# FU-AM-FU6861-B-025-HW-V1_0-20210601.net
KiCad netlist of a schematic drawn in Altium Designer
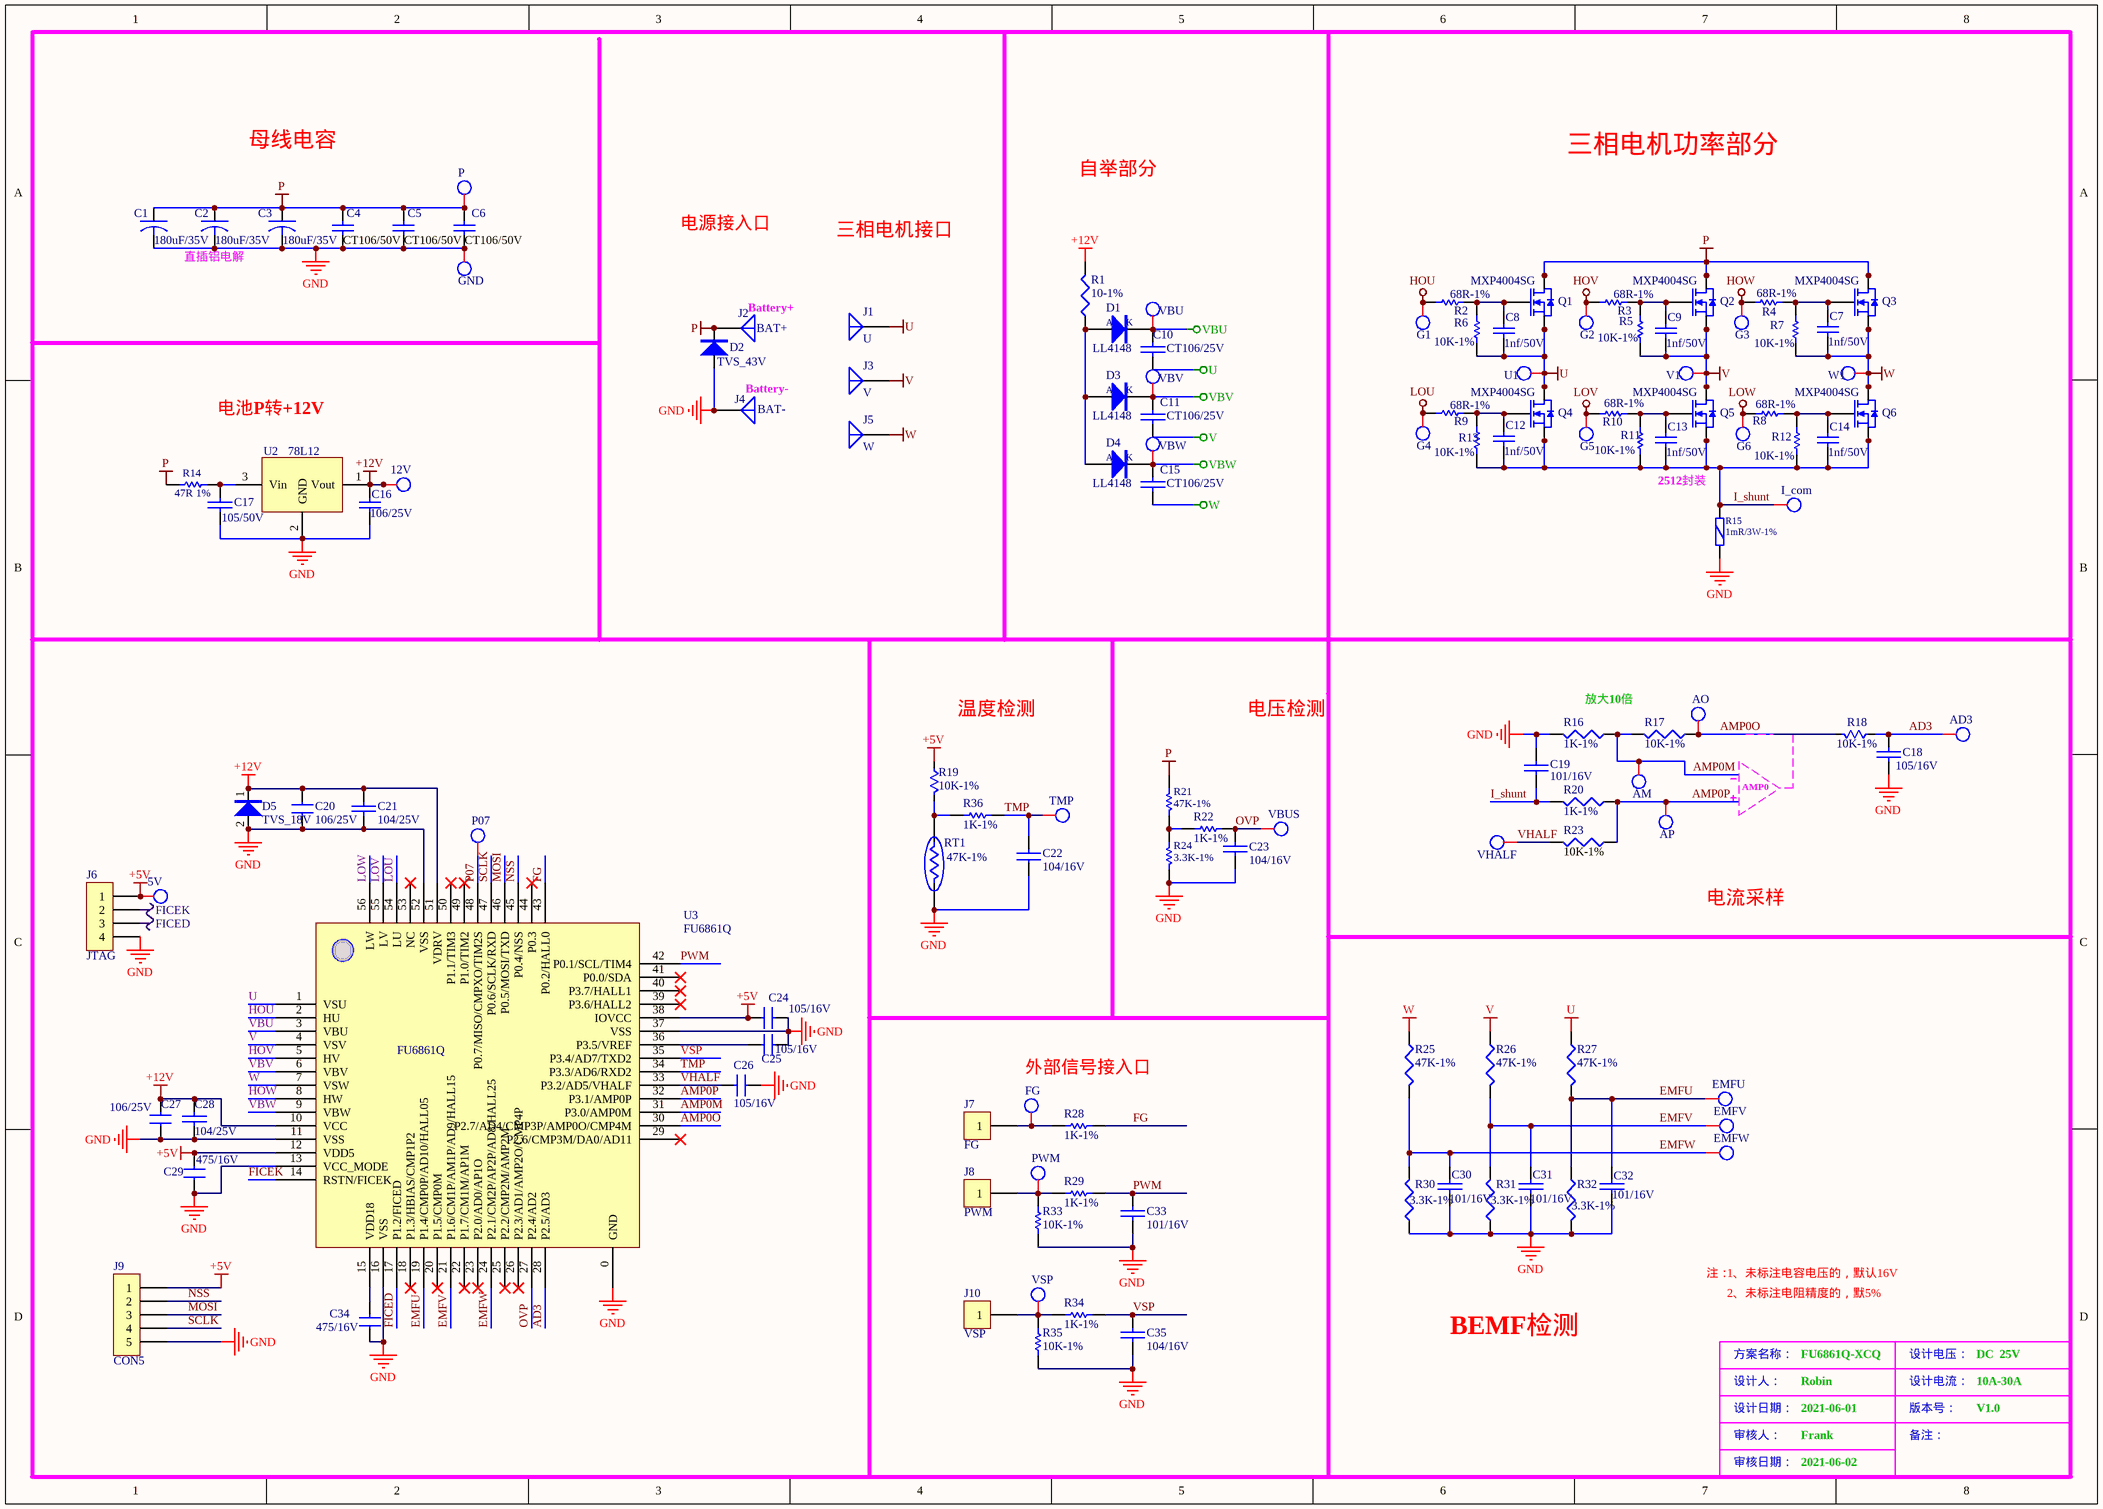
[diagram p0: FU-AM-FU6861-B-025-HW-V1.0-20210601.SCHDOC]

(export (version "E")
  (design (tool "Eeschema 10.0.6"))
  (components
    (comp (ref "5V") (value "~") (footprint "TP1.1") (libsource (lib "*") (part "Component_1")))
    (comp (ref "12V") (value "~") (footprint "TP1.1") (libsource (lib "*") (part "Component_1")))
    (comp (ref "AD3") (value "~") (footprint "TP1.1") (libsource (lib "*") (part "Component_1")))
    (comp (ref "AM") (value "~") (footprint "TP1.1") (libsource (lib "*") (part "Component_1")))
    (comp (ref "AO") (value "~") (footprint "TP1.1") (libsource (lib "*") (part "Component_1")))
    (comp (ref "AP") (value "~") (footprint "TP1.1") (libsource (lib "*") (part "Component_1")))
    (comp (ref "C1")
      (value "180uF/35V")
      (footprint "CAP2_5")
      (description "Capacitor")
      (libsource (lib "*") (part "CAPACITOR"))
    )
    (comp (ref "C2")
      (value "180uF/35V")
      (footprint "CAP2_5")
      (description "Capacitor")
      (libsource (lib "*") (part "CAPACITOR"))
    )
    (comp (ref "C3")
      (value "180uF/35V")
      (footprint "CAP2_5")
      (description "Capacitor")
      (libsource (lib "*") (part "CAPACITOR"))
    )
    (comp (ref "C4")
      (value "CT106/50V")
      (footprint "c1206")
      (description "YG-C1206K106-50V（10UF）-10%")
      (fields (field (name "PUBLISHER") "Altium Limited"))
      (libsource (lib "*") (part "Cap"))
    )
    (comp (ref "C5")
      (value "CT106/50V")
      (footprint "c1206")
      (description "YG-C1206K106-50V（10UF）-10%")
      (fields (field (name "PUBLISHER") "Altium Limited"))
      (libsource (lib "*") (part "Cap"))
    )
    (comp (ref "C6")
      (value "CT106/50V")
      (footprint "c1206")
      (description "YG-C1206K106-50V（10UF）-10%")
      (fields (field (name "PUBLISHER") "Altium Limited"))
      (libsource (lib "*") (part "Cap"))
    )
    (comp (ref "C7")
      (value "1nf/50V")
      (footprint "c0603")
      (description "YG-C1206K106-50V（10UF）-10%")
      (fields (field (name "PUBLISHER") "Altium Limited"))
      (libsource (lib "*") (part "Cap"))
    )
    (comp (ref "C8")
      (value "1nf/50V")
      (footprint "C0603")
      (description "YG-C1206K106-50V（10UF）-10%")
      (fields (field (name "PUBLISHER") "Altium Limited"))
      (libsource (lib "*") (part "Cap"))
    )
    (comp (ref "C9")
      (value "1nf/50V")
      (footprint "C0603")
      (description "YG-C1206K106-50V（10UF）-10%")
      (fields (field (name "PUBLISHER") "Altium Limited"))
      (libsource (lib "*") (part "Cap"))
    )
    (comp (ref "C10")
      (value "CT106/25V")
      (footprint "c0805")
      (description "Capacitor")
      (libsource (lib "*") (part "CAP-CC(SMD)"))
    )
    (comp (ref "C11")
      (value "CT106/25V")
      (footprint "c0805")
      (description "Capacitor")
      (libsource (lib "*") (part "CAP-CC(SMD)"))
    )
    (comp (ref "C12")
      (value "1nf/50V")
      (footprint "c0603")
      (description "YG-C1206K106-50V（10UF）-10%")
      (fields (field (name "PUBLISHER") "Altium Limited"))
      (libsource (lib "*") (part "Cap"))
    )
    (comp (ref "C13")
      (value "1nf/50V")
      (footprint "C0603")
      (description "YG-C1206K106-50V（10UF）-10%")
      (fields (field (name "PUBLISHER") "Altium Limited"))
      (libsource (lib "*") (part "Cap"))
    )
    (comp (ref "C14")
      (value "1nf/50V")
      (footprint "C0603")
      (description "YG-C1206K106-50V（10UF）-10%")
      (fields (field (name "PUBLISHER") "Altium Limited"))
      (libsource (lib "*") (part "Cap"))
    )
    (comp (ref "C15")
      (value "CT106/25V")
      (footprint "c0805")
      (description "Capacitor")
      (libsource (lib "*") (part "CAP-CC(SMD)"))
    )
    (comp (ref "C16")
      (value "106/25V")
      (footprint "C0805")
      (description "Capacitor (Semiconductor SIM Model)")
      (fields (field (name "PUBLISHER") "Altium Limited"))
      (libsource (lib "Miscellaneous Devices") (part "Cap Semi"))
    )
    (comp (ref "C17")
      (value "105/50V")
      (footprint "c1206")
      (description "Capacitor")
      (libsource (lib "") (part "CAP_2"))
    )
    (comp (ref "C18") (value "105/16V") (footprint "c0603") (libsource (lib "*") (part "CAP")))
    (comp (ref "C19")
      (value "101/16V")
      (footprint "c0603")
      (description "Capacitor")
      (libsource (lib "") (part "CAP_3"))
    )
    (comp (ref "C20")
      (value "106/25V")
      (footprint "c0805")
      (description "Capacitor")
      (libsource (lib "") (part "CAP_1"))
    )
    (comp (ref "C21")
      (value "104/25V")
      (footprint "c0603")
      (description "Capacitor")
      (libsource (lib "*") (part "CAP-CC"))
    )
    (comp (ref "C22") (value "104/16V") (footprint "c0603") (libsource (lib "*") (part "CAP NP")))
    (comp (ref "C23")
      (value "104/16V")
      (footprint "c0603")
      (description "Capacitor")
      (libsource (lib "") (part "CAP_2"))
    )
    (comp (ref "C24")
      (value "105/16V")
      (footprint "c0603")
      (description "Capacitor")
      (libsource (lib "") (part "CAP_1"))
    )
    (comp (ref "C25")
      (value "105/16V")
      (footprint "c0603")
      (description "Capacitor")
      (libsource (lib "") (part "CAP_1"))
    )
    (comp (ref "C26")
      (value "105/16V")
      (footprint "c0603")
      (description "Capacitor")
      (libsource (lib "") (part "CAP_1"))
    )
    (comp (ref "C27")
      (value "106/25V")
      (footprint "c0805")
      (description "Capacitor")
      (libsource (lib "") (part "CAP_1"))
    )
    (comp (ref "C28")
      (value "104/25V")
      (footprint "c0603")
      (description "Capacitor")
      (libsource (lib "*") (part "CAP-CC"))
    )
    (comp (ref "C29")
      (value "475/16V")
      (footprint "c0603")
      (description "Capacitor")
      (libsource (lib "") (part "CAP_1"))
    )
    (comp (ref "C30")
      (value "101/16V")
      (footprint "c0603")
      (description "Capacitor")
      (libsource (lib "") (part "CAP_3"))
    )
    (comp (ref "C31")
      (value "101/16V")
      (footprint "c0603")
      (description "Capacitor")
      (libsource (lib "") (part "CAP_3"))
    )
    (comp (ref "C32")
      (value "101/16V")
      (footprint "c0603")
      (description "Capacitor")
      (libsource (lib "") (part "CAP_3"))
    )
    (comp (ref "C33")
      (value "101/16V")
      (footprint "c0603")
      (description "Capacitor")
      (libsource (lib "") (part "CAP_2"))
    )
    (comp (ref "C34")
      (value "475/16V")
      (footprint "c0603")
      (description "Capacitor")
      (libsource (lib "") (part "CAP_1"))
    )
    (comp (ref "C35")
      (value "104/16V")
      (footprint "c0603")
      (description "Capacitor")
      (libsource (lib "") (part "CAP_2"))
    )
    (comp (ref "D1")
      (value "LL4148")
      (footprint "SOD-123")
      (description "Diode")
      (libsource (lib "*") (part "DIODE"))
    )
    (comp (ref "D2") (value "TVS_43V") (footprint "DO214AA, SMB") (libsource (lib "*") (part "D1206")))
    (comp (ref "D3")
      (value "LL4148")
      (footprint "SOD-123")
      (description "Diode")
      (libsource (lib "*") (part "DIODE"))
    )
    (comp (ref "D4")
      (value "LL4148")
      (footprint "SOD-123")
      (description "Diode")
      (libsource (lib "*") (part "DIODE"))
    )
    (comp (ref "D5") (value "TVS_18V") (footprint "DO214AC, SMA") (libsource (lib "") (part "D1206_1")))
    (comp (ref "EMFU") (value "~") (footprint "TP1.1") (libsource (lib "*") (part "Component_1")))
    (comp (ref "EMFV") (value "~") (footprint "TP1.1") (libsource (lib "*") (part "Component_1")))
    (comp (ref "EMFW") (value "~") (footprint "TP1.1") (libsource (lib "*") (part "Component_1")))
    (comp (ref "FG") (value "~") (footprint "TP1.1") (libsource (lib "*") (part "Component_1")))
    (comp (ref "G1") (value "~") (footprint "TP1.1") (libsource (lib "*") (part "Component_1")))
    (comp (ref "G2") (value "~") (footprint "TP1.1") (libsource (lib "*") (part "Component_1")))
    (comp (ref "G3") (value "~") (footprint "TP1.1") (libsource (lib "*") (part "Component_1")))
    (comp (ref "G4") (value "~") (footprint "TP1.1") (libsource (lib "*") (part "Component_1")))
    (comp (ref "G5") (value "~") (footprint "TP1.1") (libsource (lib "*") (part "Component_1")))
    (comp (ref "G6") (value "~") (footprint "TP1.1") (libsource (lib "*") (part "Component_1")))
    (comp (ref "GND") (value "~") (footprint "TP1.1") (libsource (lib "*") (part "Component_1")))
    (comp (ref "I_com") (value "~") (footprint "TP1.1") (libsource (lib "*") (part "Component_1")))
    (comp (ref "J1")
      (value "U")
      (footprint "AD")
      (description "Generic Antenna")
      (libsource (lib "") (part "ANTENNA_2"))
    )
    (comp (ref "J2")
      (value "BAT+")
      (footprint "DY")
      (description "Generic Antenna")
      (libsource (lib "*") (part "ANTENNA"))
    )
    (comp (ref "J3")
      (value "V")
      (footprint "AD")
      (description "Generic Antenna")
      (libsource (lib "") (part "ANTENNA_3"))
    )
    (comp (ref "J4")
      (value "BAT-")
      (footprint "DY")
      (description "Generic Antenna")
      (libsource (lib "*") (part "ANTENNA"))
    )
    (comp (ref "J5")
      (value "W")
      (footprint "AD")
      (description "Generic Antenna")
      (libsource (lib "") (part "ANTENNA_1"))
    )
    (comp (ref "J6")
      (value "JTAG")
      (footprint "SIP4-2")
      (description "Connector")
      (libsource (lib "*") (part "CON4"))
    )
    (comp (ref "J7")
      (value "FG")
      (footprint "tp")
      (description "Connector")
      (libsource (lib "SCH 常用封装") (part "CON1"))
    )
    (comp (ref "J8")
      (value "PWM")
      (footprint "tp")
      (description "Connector")
      (libsource (lib "SCH 常用封装") (part "CON1"))
    )
    (comp (ref "J9")
      (value "CON5")
      (footprint "SIP5-2")
      (description "Connector")
      (libsource (lib "SCH 常用封装") (part "CON5"))
    )
    (comp (ref "J10")
      (value "VSP")
      (footprint "tp")
      (description "Connector")
      (libsource (lib "SCH 常用封装") (part "CON1"))
    )
    (comp (ref "P") (value "~") (footprint "TP1.1") (libsource (lib "*") (part "Component_1")))
    (comp (ref "P07") (value "~") (footprint "TP1.1") (libsource (lib "*") (part "Component_1")))
    (comp (ref "PWM") (value "~") (footprint "TP1.1") (libsource (lib "*") (part "Component_1")))
    (comp (ref "Q1") (value "MXP4004SG") (footprint "PQFQ5X6") (libsource (lib "*") (part "MOSFET-N")))
    (comp (ref "Q2") (value "MXP4004SG") (footprint "PQFQ5X6") (libsource (lib "*") (part "MOSFET-N")))
    (comp (ref "Q3") (value "MXP4004SG") (footprint "PQFQ5X6") (libsource (lib "*") (part "MOSFET-N")))
    (comp (ref "Q4") (value "MXP4004SG") (footprint "PQFQ5X6") (libsource (lib "*") (part "MOSFET-N")))
    (comp (ref "Q5") (value "MXP4004SG") (footprint "PQFQ5X6") (libsource (lib "*") (part "MOSFET-N")))
    (comp (ref "Q6") (value "MXP4004SG") (footprint "PQFQ5X6") (libsource (lib "*") (part "MOSFET-N")))
    (comp (ref "R1") (value "10-1%") (footprint "r1206") (libsource (lib "*") (part "RES(SMD)")))
    (comp (ref "R2")
      (value "68R-1%")
      (footprint "r0603")
      (description "Semiconductor Resistor")
      (fields (field (name "PUBLISHER") "Altium Limited"))
      (libsource (lib "Miscellaneous Devices") (part "Res Semi"))
    )
    (comp (ref "R3")
      (value "68R-1%")
      (footprint "r0603")
      (description "Semiconductor Resistor")
      (fields (field (name "PUBLISHER") "Altium Limited"))
      (libsource (lib "Miscellaneous Devices") (part "Res Semi"))
    )
    (comp (ref "R4")
      (value "68R-1%")
      (footprint "r0603")
      (description "Semiconductor Resistor")
      (fields (field (name "PUBLISHER") "Altium Limited"))
      (libsource (lib "Miscellaneous Devices") (part "Res Semi"))
    )
    (comp (ref "R5")
      (value "10K-1%")
      (footprint "r0603")
      (description "YG-R0603F2002(20KΩ)-1%")
      (fields (field (name "PUBLISHER") "Altium Limited"))
      (libsource (lib "Miscellaneous Devices") (part "Res Semi"))
    )
    (comp (ref "R6")
      (value "10K-1%")
      (footprint "r0603")
      (description "YG-R0603F2002(20KΩ)-1%")
      (fields (field (name "PUBLISHER") "Altium Limited"))
      (libsource (lib "Miscellaneous Devices") (part "Res Semi"))
    )
    (comp (ref "R7")
      (value "10K-1%")
      (footprint "r0603")
      (description "YG-R0603F2002(20KΩ)-1%")
      (fields (field (name "PUBLISHER") "Altium Limited"))
      (libsource (lib "Miscellaneous Devices") (part "Res Semi"))
    )
    (comp (ref "R8")
      (value "68R-1%")
      (footprint "r0603")
      (description "Semiconductor Resistor")
      (fields (field (name "PUBLISHER") "Altium Limited"))
      (libsource (lib "Miscellaneous Devices") (part "Res Semi"))
    )
    (comp (ref "R9")
      (value "68R-1%")
      (footprint "r0603")
      (description "Semiconductor Resistor")
      (fields (field (name "PUBLISHER") "Altium Limited"))
      (libsource (lib "Miscellaneous Devices") (part "Res Semi"))
    )
    (comp (ref "R10")
      (value "68R-1%")
      (footprint "r0603")
      (description "Semiconductor Resistor")
      (fields (field (name "PUBLISHER") "Altium Limited"))
      (libsource (lib "Miscellaneous Devices") (part "Res Semi"))
    )
    (comp (ref "R11")
      (value "10K-1%")
      (footprint "r0603")
      (description "YG-R0603F2002(20KΩ)-1%")
      (fields (field (name "PUBLISHER") "Altium Limited"))
      (libsource (lib "Miscellaneous Devices") (part "Res Semi"))
    )
    (comp (ref "R12")
      (value "10K-1%")
      (footprint "r0603")
      (description "YG-R0603F2002(20KΩ)-1%")
      (fields (field (name "PUBLISHER") "Altium Limited"))
      (libsource (lib "Miscellaneous Devices") (part "Res Semi"))
    )
    (comp (ref "R13")
      (value "10K-1%")
      (footprint "r0603")
      (description "YG-R0603F2002(20KΩ)-1%")
      (fields (field (name "PUBLISHER") "Altium Limited"))
      (libsource (lib "Miscellaneous Devices") (part "Res Semi"))
    )
    (comp (ref "R14")
      (value "47R 1%")
      (footprint "R1206")
      (description "R0603F1001(1KΩ)-1%")
      (fields (field (name "PUBLISHER") "Altium Limited"))
      (libsource (lib "Miscellaneous Devices") (part "res1"))
    )
    (comp (ref "R15") (value "1mR/3W-1%") (footprint "r2512") (libsource (lib "*") (part "R-RES/2")))
    (comp (ref "R16") (value "1K-1%") (footprint "r0603") (libsource (lib "*") (part "RES(SMD)")))
    (comp (ref "R17") (value "10K-1%") (footprint "r0603") (libsource (lib "*") (part "RES(SMD)")))
    (comp (ref "R18") (value "10K-1%") (footprint "r0603") (libsource (lib "*") (part "RES3")))
    (comp (ref "R19") (value "10K-1%") (footprint "r0603") (libsource (lib "*") (part "RES3")))
    (comp (ref "R20") (value "1K-1%") (footprint "r0603") (libsource (lib "*") (part "RES(SMD)")))
    (comp (ref "R21")
      (value "47K-1%")
      (footprint "r0603")
      (description "Resistor")
      (fields (field (name "PUBLISHER") "Altium Limited"))
      (libsource (lib "Miscellaneous Devices") (part "res1"))
    )
    (comp (ref "R22")
      (value "1K-1%")
      (footprint "r0603")
      (description "Semiconductor Resistor")
      (fields (field (name "PUBLISHER") "Altium Limited"))
      (libsource (lib "Miscellaneous Devices") (part "Res Semi"))
    )
    (comp (ref "R23") (value "10K-1%") (footprint "r0603") (libsource (lib "*") (part "RES(SMD)")))
    (comp (ref "R24")
      (value "3.3K-1%")
      (footprint "r0603")
      (description "Resistor")
      (fields (field (name "PUBLISHER") "Altium Limited"))
      (libsource (lib "Miscellaneous Devices") (part "res1"))
    )
    (comp (ref "R25") (value "47K-1%") (footprint "r0603") (libsource (lib "*") (part "RES(SMD)")))
    (comp (ref "R26") (value "47K-1%") (footprint "r0603") (libsource (lib "*") (part "RES(SMD)")))
    (comp (ref "R27") (value "47K-1%") (footprint "r0603") (libsource (lib "*") (part "RES(SMD)")))
    (comp (ref "R28")
      (value "1K-1%")
      (footprint "r0603")
      (description "Semiconductor Resistor")
      (fields (field (name "PUBLISHER") "Altium Limited"))
      (libsource (lib "Miscellaneous Devices") (part "Res Semi"))
    )
    (comp (ref "R29")
      (value "1K-1%")
      (footprint "r0603")
      (description "Semiconductor Resistor")
      (fields (field (name "PUBLISHER") "Altium Limited"))
      (libsource (lib "Miscellaneous Devices") (part "Res Semi"))
    )
    (comp (ref "R30") (value "3.3K-1%") (footprint "r0603") (libsource (lib "*") (part "RES(SMD)")))
    (comp (ref "R31") (value "3.3K-1%") (footprint "r0603") (libsource (lib "*") (part "RES(SMD)")))
    (comp (ref "R32") (value "3.3K-1%") (footprint "r0603") (libsource (lib "*") (part "RES(SMD)")))
    (comp (ref "R33")
      (value "10K-1%")
      (footprint "r0603")
      (description "Semiconductor Resistor")
      (fields (field (name "PUBLISHER") "Altium Limited"))
      (libsource (lib "Miscellaneous Devices") (part "Res Semi"))
    )
    (comp (ref "R34")
      (value "1K-1%")
      (footprint "r0603")
      (description "Semiconductor Resistor")
      (fields (field (name "PUBLISHER") "Altium Limited"))
      (libsource (lib "Miscellaneous Devices") (part "Res Semi"))
    )
    (comp (ref "R35")
      (value "10K-1%")
      (footprint "r0603")
      (description "Semiconductor Resistor")
      (fields (field (name "PUBLISHER") "Altium Limited"))
      (libsource (lib "Miscellaneous Devices") (part "Res Semi"))
    )
    (comp (ref "R36")
      (value "1K-1%")
      (footprint "r0603")
      (description "Semiconductor Resistor")
      (fields (field (name "PUBLISHER") "Altium Limited"))
      (libsource (lib "Miscellaneous Devices") (part "Res Semi"))
    )
    (comp (ref "RT1")
      (value "47K-1%")
      (footprint "r0805")
      (description "Thermistor")
      (fields (field (name "PUBLISHER") "Altium Limited"))
      (libsource (lib "*") (part "Res Thermal"))
    )
    (comp (ref "TMP") (value "~") (footprint "TP1.1") (libsource (lib "*") (part "Component_1")))
    (comp (ref "U1") (value "~") (footprint "TP1.1") (libsource (lib "*") (part "Component_1")))
    (comp (ref "U2")
      (value "78L12")
      (footprint "SOT-89")
      (description "78M12")
      (libsource (lib "*") (part "VOLTREG"))
    )
    (comp (ref "U3") (value "FU6861Q") (footprint "QFN56") (libsource (lib "*") (part "FU6861Q")))
    (comp (ref "V1") (value "~") (footprint "TP1.1") (libsource (lib "*") (part "Component_1")))
    (comp (ref "VBU") (value "~") (footprint "TP1.1") (libsource (lib "*") (part "Component_1")))
    (comp (ref "VBUS") (value "~") (footprint "TP1.1") (libsource (lib "*") (part "Component_1")))
    (comp (ref "VBV") (value "~") (footprint "TP1.1") (libsource (lib "*") (part "Component_1")))
    (comp (ref "VBW") (value "~") (footprint "TP1.1") (libsource (lib "*") (part "Component_1")))
    (comp (ref "VHALF") (value "~") (footprint "TP1.1") (libsource (lib "*") (part "Component_1")))
    (comp (ref "VSP") (value "~") (footprint "TP1.1") (libsource (lib "*") (part "Component_1")))
    (comp (ref "W1") (value "~") (footprint "TP1.1") (libsource (lib "*") (part "Component_1")))
  )
  (nets
    (net (code "1") (name "+5V") (class "Default")
      (node (ref "5V") (pin "1") (pinfunction "0_1") (pintype "passive"))
      (node (ref "C24") (pin "1") (pinfunction "1_1") (pintype "passive"))
      (node (ref "C29") (pin "1") (pinfunction "1_1") (pintype "passive"))
      (node (ref "J6") (pin "1") (pinfunction "1_1") (pintype "passive"))
      (node (ref "J9") (pin "1") (pinfunction "1_1") (pintype "passive"))
      (node (ref "R19") (pin "1") (pintype "passive"))
      (node (ref "U3") (pin "12") (pinfunction "VDD5_12") (pintype "passive"))
      (node (ref "U3") (pin "38") (pinfunction "IOVCC_38") (pintype "passive"))
    )
    (net (code "2") (name "+12V") (class "Default")
      (node (ref "12V") (pin "1") (pinfunction "0_1") (pintype "passive"))
      (node (ref "C16") (pin "2") (pinfunction "2_2") (pintype "passive"))
      (node (ref "C20") (pin "2") (pinfunction "2_2") (pintype "passive"))
      (node (ref "C21") (pin "2") (pinfunction "2_2") (pintype "passive"))
      (node (ref "C27") (pin "2") (pinfunction "2_2") (pintype "passive"))
      (node (ref "C28") (pin "1") (pinfunction "1_1") (pintype "passive"))
      (node (ref "D5") (pin "1") (pinfunction "1_1") (pintype "passive"))
      (node (ref "R1") (pin "2") (pinfunction "2_2") (pintype "passive"))
      (node (ref "U2") (pin "1") (pinfunction "Vout_1") (pintype "passive"))
      (node (ref "U3") (pin "10") (pinfunction "VCC_10") (pintype "passive"))
      (node (ref "U3") (pin "51") (pinfunction "VDRV_51") (pintype "passive"))
    )
    (net (code "3") (name "/AD3") (class "Default")
      (node (ref "AD3") (pin "1") (pinfunction "0_1") (pintype "passive"))
      (node (ref "C18") (pin "1") (pintype "passive"))
      (node (ref "R18") (pin "1") (pintype "passive"))
      (node (ref "U3") (pin "28") (pinfunction "P2.5/AD3_28") (pintype "passive"))
    )
    (net (code "4") (name "/AMP0M") (class "Default")
      (node (ref "AM") (pin "1") (pinfunction "0_1") (pintype "passive"))
      (node (ref "R16") (pin "1") (pinfunction "1_1") (pintype "passive"))
      (node (ref "R17") (pin "2") (pinfunction "2_2") (pintype "passive"))
      (node (ref "U3") (pin "31") (pinfunction "P3.0/AMP0M_31") (pintype "passive"))
    )
    (net (code "5") (name "/AMP0O") (class "Default")
      (node (ref "AO") (pin "1") (pinfunction "0_1") (pintype "passive"))
      (node (ref "R17") (pin "1") (pinfunction "1_1") (pintype "passive"))
      (node (ref "R18") (pin "2") (pintype "passive"))
      (node (ref "U3") (pin "30") (pinfunction "P2.7/AD4/CMP3P/AMP0O/CMP4M_30") (pintype "passive"))
    )
    (net (code "6") (name "/AMP0P") (class "Default")
      (node (ref "AP") (pin "1") (pinfunction "0_1") (pintype "passive"))
      (node (ref "R20") (pin "1") (pinfunction "1_1") (pintype "passive"))
      (node (ref "R23") (pin "1") (pinfunction "1_1") (pintype "passive"))
      (node (ref "U3") (pin "32") (pinfunction "P3.1/AMP0P_32") (pintype "passive"))
    )
    (net (code "7") (name "/EMFU") (class "Default")
      (node (ref "C32") (pin "2") (pinfunction "2_2") (pintype "passive"))
      (node (ref "EMFU") (pin "1") (pinfunction "0_1") (pintype "passive"))
      (node (ref "R27") (pin "2") (pinfunction "2_2") (pintype "passive"))
      (node (ref "R32") (pin "1") (pinfunction "1_1") (pintype "passive"))
      (node (ref "U3") (pin "19") (pinfunction "P1.4/CMP0P/AD10/HALL05_19") (pintype "passive"))
    )
    (net (code "8") (name "/EMFV") (class "Default")
      (node (ref "C31") (pin "1") (pinfunction "1_1") (pintype "passive"))
      (node (ref "EMFV") (pin "1") (pinfunction "0_1") (pintype "passive"))
      (node (ref "R26") (pin "2") (pinfunction "2_2") (pintype "passive"))
      (node (ref "R31") (pin "2") (pinfunction "2_2") (pintype "passive"))
      (node (ref "U3") (pin "21") (pinfunction "P1.6/CM1P/AM1P/AD9/HALL15_21") (pintype "passive"))
    )
    (net (code "9") (name "/EMFW") (class "Default")
      (node (ref "C30") (pin "1") (pinfunction "1_1") (pintype "passive"))
      (node (ref "EMFW") (pin "1") (pinfunction "0_1") (pintype "passive"))
      (node (ref "R25") (pin "2") (pinfunction "2_2") (pintype "passive"))
      (node (ref "R30") (pin "2") (pinfunction "2_2") (pintype "passive"))
      (node (ref "U3") (pin "24") (pinfunction "P2.1/CM2P/AP2P/AD8/HALL25_24") (pintype "passive"))
    )
    (net (code "10") (name "/FG") (class "Default")
      (node (ref "R28") (pin "2") (pinfunction "2_2") (pintype "passive"))
      (node (ref "U3") (pin "43") (pinfunction "P0.2/HALL0_43") (pintype "passive"))
    )
    (net (code "11") (name "/I_shunt") (class "Default")
      (node (ref "C12") (pin "1") (pinfunction "1_1") (pintype "passive"))
      (node (ref "C13") (pin "1") (pinfunction "1_1") (pintype "passive"))
      (node (ref "C14") (pin "1") (pinfunction "1_1") (pintype "passive"))
      (node (ref "C19") (pin "2") (pinfunction "2_2") (pintype "passive"))
      (node (ref "I_com") (pin "1") (pinfunction "0_1") (pintype "passive"))
      (node (ref "Q4") (pin "1") (pinfunction "S_1") (pintype "passive"))
      (node (ref "Q4") (pin "2") (pinfunction "S_2") (pintype "passive"))
      (node (ref "Q4") (pin "3") (pinfunction "S_3") (pintype "passive"))
      (node (ref "Q5") (pin "1") (pinfunction "S_1") (pintype "passive"))
      (node (ref "Q5") (pin "2") (pinfunction "S_2") (pintype "passive"))
      (node (ref "Q5") (pin "3") (pinfunction "S_3") (pintype "passive"))
      (node (ref "Q6") (pin "1") (pinfunction "S_1") (pintype "passive"))
      (node (ref "Q6") (pin "2") (pinfunction "S_2") (pintype "passive"))
      (node (ref "Q6") (pin "3") (pinfunction "S_3") (pintype "passive"))
      (node (ref "R11") (pin "1") (pinfunction "1_1") (pintype "passive"))
      (node (ref "R12") (pin "1") (pinfunction "1_1") (pintype "passive"))
      (node (ref "R13") (pin "1") (pinfunction "1_1") (pintype "passive"))
      (node (ref "R15") (pin "2") (pinfunction "2_2") (pintype "passive"))
      (node (ref "R20") (pin "2") (pinfunction "2_2") (pintype "passive"))
    )
    (net (code "12") (name "/MOSI") (class "Default")
      (node (ref "J9") (pin "3") (pinfunction "3_3") (pintype "passive"))
      (node (ref "U3") (pin "46") (pinfunction "P0.5/MOSI/TXD_46") (pintype "passive"))
    )
    (net (code "13") (name "/NSS") (class "Default")
      (node (ref "J9") (pin "2") (pinfunction "2_2") (pintype "passive"))
      (node (ref "U3") (pin "45") (pinfunction "P0.4/NSS_45") (pintype "passive"))
    )
    (net (code "14") (name "/OVP") (class "Default")
      (node (ref "C23") (pin "1") (pinfunction "1_1") (pintype "passive"))
      (node (ref "R22") (pin "2") (pinfunction "2_2") (pintype "passive"))
      (node (ref "U3") (pin "27") (pinfunction "P2.4/AD2_27") (pintype "passive"))
      (node (ref "VBUS") (pin "1") (pinfunction "0_1") (pintype "passive"))
    )
    (net (code "15") (name "/P07") (class "Default")
      (node (ref "P07") (pin "1") (pinfunction "0_1") (pintype "passive"))
      (node (ref "U3") (pin "48") (pinfunction "P0.7/MISO/CMPXO/TIM2S_48") (pintype "passive"))
    )
    (net (code "16") (name "/PWM") (class "Default")
      (node (ref "C33") (pin "2") (pinfunction "2_2") (pintype "passive"))
      (node (ref "R29") (pin "2") (pinfunction "2_2") (pintype "passive"))
      (node (ref "U3") (pin "42") (pinfunction "P0.1/SCL/TIM4_42") (pintype "passive"))
    )
    (net (code "17") (name "/SCLK") (class "Default")
      (node (ref "J9") (pin "4") (pinfunction "4_4") (pintype "passive"))
      (node (ref "U3") (pin "47") (pinfunction "P0.6/SCLK/RXD_47") (pintype "passive"))
    )
    (net (code "18") (name "/TMP") (class "Default")
      (node (ref "C22") (pin "2") (pinfunction "2_2") (pintype "passive"))
      (node (ref "R36") (pin "2") (pinfunction "2_2") (pintype "passive"))
      (node (ref "TMP") (pin "1") (pinfunction "0_1") (pintype "passive"))
      (node (ref "U3") (pin "34") (pinfunction "P3.3/AD6/RXD2_34") (pintype "passive"))
    )
    (net (code "19") (name "/VHALF") (class "Default")
      (node (ref "C26") (pin "1") (pinfunction "1_1") (pintype "passive"))
      (node (ref "R23") (pin "2") (pinfunction "2_2") (pintype "passive"))
      (node (ref "U3") (pin "33") (pinfunction "P3.2/AD5/VHALF_33") (pintype "passive"))
      (node (ref "VHALF") (pin "1") (pinfunction "0_1") (pintype "passive"))
    )
    (net (code "20") (name "/VSP") (class "Default")
      (node (ref "C35") (pin "2") (pinfunction "2_2") (pintype "passive"))
      (node (ref "R34") (pin "2") (pinfunction "2_2") (pintype "passive"))
      (node (ref "U3") (pin "35") (pinfunction "P3.4/AD7/TXD2_35") (pintype "passive"))
    )
    (net (code "21") (name "FICED") (class "Default")
      (node (ref "J6") (pin "3") (pinfunction "3_3") (pintype "passive"))
      (node (ref "U3") (pin "17") (pinfunction "P1.2/FICED_17") (pintype "passive"))
    )
    (net (code "22") (name "FICEK") (class "Default")
      (node (ref "J6") (pin "2") (pinfunction "2_2") (pintype "passive"))
      (node (ref "U3") (pin "14") (pinfunction "RSTN/FICEK_14") (pintype "passive"))
    )
    (net (code "23") (name "GND") (class "Default")
      (node (ref "C1") (pin "2") (pinfunction "2_2") (pintype "passive"))
      (node (ref "C16") (pin "1") (pinfunction "1_1") (pintype "passive"))
      (node (ref "C17") (pin "2") (pinfunction "2_2") (pintype "passive"))
      (node (ref "C18") (pin "2") (pintype "passive"))
      (node (ref "C19") (pin "1") (pinfunction "1_1") (pintype "passive"))
      (node (ref "C2") (pin "2") (pinfunction "2_2") (pintype "passive"))
      (node (ref "C20") (pin "1") (pinfunction "1_1") (pintype "passive"))
      (node (ref "C21") (pin "1") (pinfunction "1_1") (pintype "passive"))
      (node (ref "C22") (pin "1") (pinfunction "1_1") (pintype "passive"))
      (node (ref "C23") (pin "2") (pinfunction "2_2") (pintype "passive"))
      (node (ref "C24") (pin "2") (pinfunction "2_2") (pintype "passive"))
      (node (ref "C25") (pin "1") (pinfunction "1_1") (pintype "passive"))
      (node (ref "C26") (pin "2") (pinfunction "2_2") (pintype "passive"))
      (node (ref "C27") (pin "1") (pinfunction "1_1") (pintype "passive"))
      (node (ref "C28") (pin "2") (pinfunction "2_2") (pintype "passive"))
      (node (ref "C29") (pin "2") (pinfunction "2_2") (pintype "passive"))
      (node (ref "C3") (pin "2") (pinfunction "2_2") (pintype "passive"))
      (node (ref "C30") (pin "2") (pinfunction "2_2") (pintype "passive"))
      (node (ref "C31") (pin "2") (pinfunction "2_2") (pintype "passive"))
      (node (ref "C32") (pin "1") (pinfunction "1_1") (pintype "passive"))
      (node (ref "C33") (pin "1") (pinfunction "1_1") (pintype "passive"))
      (node (ref "C34") (pin "2") (pinfunction "2_2") (pintype "passive"))
      (node (ref "C35") (pin "1") (pinfunction "1_1") (pintype "passive"))
      (node (ref "C4") (pin "1") (pinfunction "1_1") (pintype "passive"))
      (node (ref "C5") (pin "1") (pinfunction "1_1") (pintype "passive"))
      (node (ref "C6") (pin "1") (pinfunction "1_1") (pintype "passive"))
      (node (ref "D2") (pin "2") (pinfunction "2_2") (pintype "passive"))
      (node (ref "D5") (pin "2") (pinfunction "2_2") (pintype "passive"))
      (node (ref "GND") (pin "1") (pinfunction "0_1") (pintype "passive"))
      (node (ref "J4") (pin "1") (pinfunction "GND_1") (pintype "passive"))
      (node (ref "J6") (pin "4") (pinfunction "4_4") (pintype "passive"))
      (node (ref "J9") (pin "5") (pinfunction "5_5") (pintype "passive"))
      (node (ref "R15") (pin "1") (pinfunction "1_1") (pintype "passive"))
      (node (ref "R16") (pin "2") (pinfunction "2_2") (pintype "passive"))
      (node (ref "R24") (pin "2") (pinfunction "2_2") (pintype "passive"))
      (node (ref "R30") (pin "1") (pinfunction "1_1") (pintype "passive"))
      (node (ref "R31") (pin "1") (pinfunction "1_1") (pintype "passive"))
      (node (ref "R32") (pin "2") (pinfunction "2_2") (pintype "passive"))
      (node (ref "R33") (pin "1") (pinfunction "1_1") (pintype "passive"))
      (node (ref "R35") (pin "1") (pinfunction "1_1") (pintype "passive"))
      (node (ref "RT1") (pin "2") (pinfunction "2_2") (pintype "passive"))
      (node (ref "U2") (pin "2") (pinfunction "GND_2") (pintype "passive"))
      (node (ref "U3") (pin "0") (pinfunction "GND_0") (pintype "passive"))
      (node (ref "U3") (pin "11") (pinfunction "VSS_11") (pintype "passive"))
      (node (ref "U3") (pin "13") (pinfunction "VCC_MODE_13") (pintype "passive"))
      (node (ref "U3") (pin "16") (pinfunction "VSS_16") (pintype "passive"))
      (node (ref "U3") (pin "37") (pinfunction "VSS_37") (pintype "passive"))
      (node (ref "U3") (pin "52") (pinfunction "VSS_52") (pintype "passive"))
    )
    (net (code "24") (name "HOU") (class "Default")
      (node (ref "G1") (pin "1") (pinfunction "0_1") (pintype "passive"))
      (node (ref "R2") (pin "1") (pinfunction "1_1") (pintype "passive"))
      (node (ref "U3") (pin "2") (pinfunction "HU_2") (pintype "passive"))
    )
    (net (code "25") (name "HOV") (class "Default")
      (node (ref "G2") (pin "1") (pinfunction "0_1") (pintype "passive"))
      (node (ref "R3") (pin "1") (pinfunction "1_1") (pintype "passive"))
      (node (ref "U3") (pin "5") (pinfunction "HV_5") (pintype "passive"))
    )
    (net (code "26") (name "HOW") (class "Default")
      (node (ref "G3") (pin "1") (pinfunction "0_1") (pintype "passive"))
      (node (ref "R4") (pin "1") (pinfunction "1_1") (pintype "passive"))
      (node (ref "U3") (pin "8") (pinfunction "HW_8") (pintype "passive"))
    )
    (net (code "27") (name "LOU") (class "Default")
      (node (ref "G4") (pin "1") (pinfunction "0_1") (pintype "passive"))
      (node (ref "R9") (pin "1") (pinfunction "1_1") (pintype "passive"))
      (node (ref "U3") (pin "54") (pinfunction "LU_54") (pintype "passive"))
    )
    (net (code "28") (name "LOV") (class "Default")
      (node (ref "G5") (pin "1") (pinfunction "0_1") (pintype "passive"))
      (node (ref "R10") (pin "1") (pinfunction "1_1") (pintype "passive"))
      (node (ref "U3") (pin "55") (pinfunction "LV_55") (pintype "passive"))
    )
    (net (code "29") (name "LOW") (class "Default")
      (node (ref "G6") (pin "1") (pinfunction "0_1") (pintype "passive"))
      (node (ref "R8") (pin "1") (pinfunction "1_1") (pintype "passive"))
      (node (ref "U3") (pin "56") (pinfunction "LW_56") (pintype "passive"))
    )
    (net (code "30") (name "Net-(D1-Pad1)") (class "Default")
      (node (ref "D1") (pin "1") (pinfunction "1_1") (pintype "passive"))
      (node (ref "D3") (pin "1") (pinfunction "1_1") (pintype "passive"))
      (node (ref "D4") (pin "1") (pinfunction "1_1") (pintype "passive"))
      (node (ref "R1") (pin "1") (pinfunction "1_1") (pintype "passive"))
    )
    (net (code "31") (name "Net-(FG-0)") (class "Default")
      (node (ref "FG") (pin "1") (pinfunction "0_1") (pintype "passive"))
      (node (ref "J7") (pin "1") (pinfunction "1_1") (pintype "passive"))
      (node (ref "R28") (pin "1") (pinfunction "1_1") (pintype "passive"))
    )
    (net (code "32") (name "Net-(PWM-0)") (class "Default")
      (node (ref "J8") (pin "1") (pinfunction "1_1") (pintype "passive"))
      (node (ref "PWM") (pin "1") (pinfunction "0_1") (pintype "passive"))
      (node (ref "R29") (pin "1") (pinfunction "1_1") (pintype "passive"))
      (node (ref "R33") (pin "2") (pinfunction "2_2") (pintype "passive"))
    )
    (net (code "33") (name "Net-(Q1-G)") (class "Default")
      (node (ref "C8") (pin "2") (pinfunction "2_2") (pintype "passive"))
      (node (ref "Q1") (pin "4") (pinfunction "G_4") (pintype "passive"))
      (node (ref "R2") (pin "2") (pinfunction "2_2") (pintype "passive"))
      (node (ref "R6") (pin "2") (pinfunction "2_2") (pintype "passive"))
    )
    (net (code "34") (name "Net-(Q2-G)") (class "Default")
      (node (ref "C9") (pin "2") (pinfunction "2_2") (pintype "passive"))
      (node (ref "Q2") (pin "4") (pinfunction "G_4") (pintype "passive"))
      (node (ref "R3") (pin "2") (pinfunction "2_2") (pintype "passive"))
      (node (ref "R5") (pin "2") (pinfunction "2_2") (pintype "passive"))
    )
    (net (code "35") (name "Net-(Q3-G)") (class "Default")
      (node (ref "C7") (pin "2") (pinfunction "2_2") (pintype "passive"))
      (node (ref "Q3") (pin "4") (pinfunction "G_4") (pintype "passive"))
      (node (ref "R4") (pin "2") (pinfunction "2_2") (pintype "passive"))
      (node (ref "R7") (pin "2") (pinfunction "2_2") (pintype "passive"))
    )
    (net (code "36") (name "Net-(Q4-G)") (class "Default")
      (node (ref "C12") (pin "2") (pinfunction "2_2") (pintype "passive"))
      (node (ref "Q4") (pin "4") (pinfunction "G_4") (pintype "passive"))
      (node (ref "R13") (pin "2") (pinfunction "2_2") (pintype "passive"))
      (node (ref "R9") (pin "2") (pinfunction "2_2") (pintype "passive"))
    )
    (net (code "37") (name "Net-(Q5-G)") (class "Default")
      (node (ref "C13") (pin "2") (pinfunction "2_2") (pintype "passive"))
      (node (ref "Q5") (pin "4") (pinfunction "G_4") (pintype "passive"))
      (node (ref "R10") (pin "2") (pinfunction "2_2") (pintype "passive"))
      (node (ref "R11") (pin "2") (pinfunction "2_2") (pintype "passive"))
    )
    (net (code "38") (name "Net-(Q6-G)") (class "Default")
      (node (ref "C14") (pin "2") (pinfunction "2_2") (pintype "passive"))
      (node (ref "Q6") (pin "4") (pinfunction "G_4") (pintype "passive"))
      (node (ref "R12") (pin "2") (pinfunction "2_2") (pintype "passive"))
      (node (ref "R8") (pin "2") (pinfunction "2_2") (pintype "passive"))
    )
    (net (code "39") (name "Net-(R19-Pad2)") (class "Default")
      (node (ref "R19") (pin "2") (pintype "passive"))
      (node (ref "R36") (pin "1") (pinfunction "1_1") (pintype "passive"))
      (node (ref "RT1") (pin "1") (pinfunction "1_1") (pintype "passive"))
    )
    (net (code "40") (name "Net-(R21-Pad2)") (class "Default")
      (node (ref "R21") (pin "2") (pinfunction "2_2") (pintype "passive"))
      (node (ref "R22") (pin "1") (pinfunction "1_1") (pintype "passive"))
      (node (ref "R24") (pin "1") (pinfunction "1_1") (pintype "passive"))
    )
    (net (code "41") (name "Net-(U2-Vin)") (class "Default")
      (node (ref "C17") (pin "1") (pinfunction "1_1") (pintype "passive"))
      (node (ref "R14") (pin "2") (pinfunction "2_2") (pintype "passive"))
      (node (ref "U2") (pin "3") (pinfunction "Vin_3") (pintype "passive"))
    )
    (net (code "42") (name "Net-(U3-P3.5{slash}VREF)") (class "Default")
      (node (ref "C25") (pin "2") (pinfunction "2_2") (pintype "passive"))
      (node (ref "U3") (pin "36") (pinfunction "P3.5/VREF_36") (pintype "passive"))
    )
    (net (code "43") (name "Net-(U3-VDD18)") (class "Default")
      (node (ref "C34") (pin "1") (pinfunction "1_1") (pintype "passive"))
      (node (ref "U3") (pin "15") (pinfunction "VDD18_15") (pintype "passive"))
    )
    (net (code "44") (name "Net-(VSP-0)") (class "Default")
      (node (ref "J10") (pin "1") (pinfunction "1_1") (pintype "passive"))
      (node (ref "R34") (pin "1") (pinfunction "1_1") (pintype "passive"))
      (node (ref "R35") (pin "2") (pinfunction "2_2") (pintype "passive"))
      (node (ref "VSP") (pin "1") (pinfunction "0_1") (pintype "passive"))
    )
    (net (code "45") (name "P") (class "Default")
      (node (ref "C1") (pin "1") (pinfunction "1_1") (pintype "passive"))
      (node (ref "C2") (pin "1") (pinfunction "1_1") (pintype "passive"))
      (node (ref "C3") (pin "1") (pinfunction "1_1") (pintype "passive"))
      (node (ref "C4") (pin "2") (pinfunction "2_2") (pintype "passive"))
      (node (ref "C5") (pin "2") (pinfunction "2_2") (pintype "passive"))
      (node (ref "C6") (pin "2") (pinfunction "2_2") (pintype "passive"))
      (node (ref "D2") (pin "1") (pinfunction "1_1") (pintype "passive"))
      (node (ref "J2") (pin "1") (pinfunction "GND_1") (pintype "passive"))
      (node (ref "P") (pin "1") (pinfunction "0_1") (pintype "passive"))
      (node (ref "Q1") (pin "5") (pinfunction "D_5") (pintype "passive"))
      (node (ref "Q1") (pin "6") (pinfunction "D_6") (pintype "passive"))
      (node (ref "Q1") (pin "7") (pinfunction "D_7") (pintype "passive"))
      (node (ref "Q1") (pin "8") (pinfunction "D_8") (pintype "passive"))
      (node (ref "Q2") (pin "5") (pinfunction "D_5") (pintype "passive"))
      (node (ref "Q2") (pin "6") (pinfunction "D_6") (pintype "passive"))
      (node (ref "Q2") (pin "7") (pinfunction "D_7") (pintype "passive"))
      (node (ref "Q2") (pin "8") (pinfunction "D_8") (pintype "passive"))
      (node (ref "Q3") (pin "5") (pinfunction "D_5") (pintype "passive"))
      (node (ref "Q3") (pin "6") (pinfunction "D_6") (pintype "passive"))
      (node (ref "Q3") (pin "7") (pinfunction "D_7") (pintype "passive"))
      (node (ref "Q3") (pin "8") (pinfunction "D_8") (pintype "passive"))
      (node (ref "R14") (pin "1") (pinfunction "1_1") (pintype "passive"))
      (node (ref "R21") (pin "1") (pinfunction "1_1") (pintype "passive"))
    )
    (net (code "46") (name "U") (class "Default")
      (node (ref "C10") (pin "1") (pinfunction "1_1") (pintype "passive"))
      (node (ref "C8") (pin "1") (pinfunction "1_1") (pintype "passive"))
      (node (ref "J1") (pin "1") (pinfunction "U_1") (pintype "passive"))
      (node (ref "Q1") (pin "1") (pinfunction "S_1") (pintype "passive"))
      (node (ref "Q1") (pin "2") (pinfunction "S_2") (pintype "passive"))
      (node (ref "Q1") (pin "3") (pinfunction "S_3") (pintype "passive"))
      (node (ref "Q4") (pin "5") (pinfunction "D_5") (pintype "passive"))
      (node (ref "Q4") (pin "6") (pinfunction "D_6") (pintype "passive"))
      (node (ref "Q4") (pin "7") (pinfunction "D_7") (pintype "passive"))
      (node (ref "Q4") (pin "8") (pinfunction "D_8") (pintype "passive"))
      (node (ref "R27") (pin "1") (pinfunction "1_1") (pintype "passive"))
      (node (ref "R6") (pin "1") (pinfunction "1_1") (pintype "passive"))
      (node (ref "U1") (pin "1") (pinfunction "0_1") (pintype "passive"))
      (node (ref "U3") (pin "1") (pinfunction "VSU_1") (pintype "passive"))
    )
    (net (code "47") (name "V") (class "Default")
      (node (ref "C11") (pin "1") (pinfunction "1_1") (pintype "passive"))
      (node (ref "C9") (pin "1") (pinfunction "1_1") (pintype "passive"))
      (node (ref "J3") (pin "1") (pinfunction "V_1") (pintype "passive"))
      (node (ref "Q2") (pin "1") (pinfunction "S_1") (pintype "passive"))
      (node (ref "Q2") (pin "2") (pinfunction "S_2") (pintype "passive"))
      (node (ref "Q2") (pin "3") (pinfunction "S_3") (pintype "passive"))
      (node (ref "Q5") (pin "5") (pinfunction "D_5") (pintype "passive"))
      (node (ref "Q5") (pin "6") (pinfunction "D_6") (pintype "passive"))
      (node (ref "Q5") (pin "7") (pinfunction "D_7") (pintype "passive"))
      (node (ref "Q5") (pin "8") (pinfunction "D_8") (pintype "passive"))
      (node (ref "R26") (pin "1") (pinfunction "1_1") (pintype "passive"))
      (node (ref "R5") (pin "1") (pinfunction "1_1") (pintype "passive"))
      (node (ref "U3") (pin "4") (pinfunction "VSV_4") (pintype "passive"))
      (node (ref "V1") (pin "1") (pinfunction "0_1") (pintype "passive"))
    )
    (net (code "48") (name "VBU") (class "Default")
      (node (ref "C10") (pin "2") (pinfunction "2_2") (pintype "passive"))
      (node (ref "D1") (pin "2") (pinfunction "2_2") (pintype "passive"))
      (node (ref "U3") (pin "3") (pinfunction "VBU_3") (pintype "passive"))
      (node (ref "VBU") (pin "1") (pinfunction "0_1") (pintype "passive"))
    )
    (net (code "49") (name "VBV") (class "Default")
      (node (ref "C11") (pin "2") (pinfunction "2_2") (pintype "passive"))
      (node (ref "D3") (pin "2") (pinfunction "2_2") (pintype "passive"))
      (node (ref "U3") (pin "6") (pinfunction "VBV_6") (pintype "passive"))
      (node (ref "VBV") (pin "1") (pinfunction "0_1") (pintype "passive"))
    )
    (net (code "50") (name "VBW") (class "Default")
      (node (ref "C15") (pin "2") (pinfunction "2_2") (pintype "passive"))
      (node (ref "D4") (pin "2") (pinfunction "2_2") (pintype "passive"))
      (node (ref "U3") (pin "9") (pinfunction "VBW_9") (pintype "passive"))
      (node (ref "VBW") (pin "1") (pinfunction "0_1") (pintype "passive"))
    )
    (net (code "51") (name "W") (class "Default")
      (node (ref "C15") (pin "1") (pinfunction "1_1") (pintype "passive"))
      (node (ref "C7") (pin "1") (pinfunction "1_1") (pintype "passive"))
      (node (ref "J5") (pin "1") (pinfunction "W_1") (pintype "passive"))
      (node (ref "Q3") (pin "1") (pinfunction "S_1") (pintype "passive"))
      (node (ref "Q3") (pin "2") (pinfunction "S_2") (pintype "passive"))
      (node (ref "Q3") (pin "3") (pinfunction "S_3") (pintype "passive"))
      (node (ref "Q6") (pin "5") (pinfunction "D_5") (pintype "passive"))
      (node (ref "Q6") (pin "6") (pinfunction "D_6") (pintype "passive"))
      (node (ref "Q6") (pin "7") (pinfunction "D_7") (pintype "passive"))
      (node (ref "Q6") (pin "8") (pinfunction "D_8") (pintype "passive"))
      (node (ref "R25") (pin "1") (pinfunction "1_1") (pintype "passive"))
      (node (ref "R7") (pin "1") (pinfunction "1_1") (pintype "passive"))
      (node (ref "U3") (pin "7") (pinfunction "VSW_7") (pintype "passive"))
      (node (ref "W1") (pin "1") (pinfunction "0_1") (pintype "passive"))
    )
    (net (code "52") (name "unconnected-(U3-NC-Pad53)") (class "Default")
      (node (ref "U3") (pin "53") (pinfunction "NC_53") (pintype "passive+no_connect"))
    )
    (net (code "53") (name "unconnected-(U3-P0.0{slash}SDA-Pad41)") (class "Default")
      (node (ref "U3") (pin "41") (pinfunction "P0.0/SDA_41") (pintype "passive+no_connect"))
    )
    (net (code "54") (name "unconnected-(U3-P0.3-Pad44)") (class "Default")
      (node (ref "U3") (pin "44") (pinfunction "P0.3_44") (pintype "passive+no_connect"))
    )
    (net (code "55") (name "unconnected-(U3-P1.0{slash}TIM2-Pad49)") (class "Default")
      (node (ref "U3") (pin "49") (pinfunction "P1.0/TIM2_49") (pintype "passive+no_connect"))
    )
    (net (code "56") (name "unconnected-(U3-P1.1{slash}TIM3-Pad50)") (class "Default")
      (node (ref "U3") (pin "50") (pinfunction "P1.1/TIM3_50") (pintype "passive+no_connect"))
    )
    (net (code "57") (name "unconnected-(U3-P1.3{slash}HBIAS{slash}CMP1P2-Pad18)") (class "Default")
      (node (ref "U3") (pin "18") (pinfunction "P1.3/HBIAS/CMP1P2_18") (pintype "passive+no_connect"))
    )
    (net (code "58") (name "unconnected-(U3-P1.5{slash}CMP0M-Pad20)") (class "Default")
      (node (ref "U3") (pin "20") (pinfunction "P1.5/CMP0M_20") (pintype "passive+no_connect"))
    )
    (net (code "59") (name "unconnected-(U3-P1.7{slash}CM1M{slash}AP1M-Pad22)") (class "Default")
      (node (ref "U3") (pin "22") (pinfunction "P1.7/CM1M/AP1M_22") (pintype "passive+no_connect"))
    )
    (net (code "60") (name "unconnected-(U3-P2.0{slash}AD0{slash}AP1O-Pad23)") (class "Default")
      (node (ref "U3") (pin "23") (pinfunction "P2.0/AD0/AP1O_23") (pintype "passive+no_connect"))
    )
    (net (code "61") (name "unconnected-(U3-P2.2{slash}CMP2M{slash}AMP2M-Pad25)") (class "Default")
      (node (ref "U3") (pin "25") (pinfunction "P2.2/CMP2M/AMP2M_25") (pintype "passive+no_connect"))
    )
    (net (code "62") (name "unconnected-(U3-P2.3{slash}AD1{slash}AMP2O{slash}CMP4P-Pad26)") (class "Default")
      (node (ref "U3") (pin "26") (pinfunction "P2.3/AD1/AMP2O/CMP4P_26") (pintype "passive+no_connect"))
    )
    (net (code "63") (name "unconnected-(U3-P2.6{slash}CMP3M{slash}DA0{slash}AD11-Pad29)") (class "Default")
      (node (ref "U3") (pin "29") (pinfunction "P2.6/CMP3M/DA0/AD11_29") (pintype "passive+no_connect"))
    )
    (net (code "64") (name "unconnected-(U3-P3.6{slash}HALL2-Pad39)") (class "Default")
      (node (ref "U3") (pin "39") (pinfunction "P3.6/HALL2_39") (pintype "passive+no_connect"))
    )
    (net (code "65") (name "unconnected-(U3-P3.7{slash}HALL1-Pad40)") (class "Default")
      (node (ref "U3") (pin "40") (pinfunction "P3.7/HALL1_40") (pintype "passive+no_connect"))
    )
  )
)
